# AUDIO_CODEC.net
KiCad netlist of a schematic drawn in Altium Designer
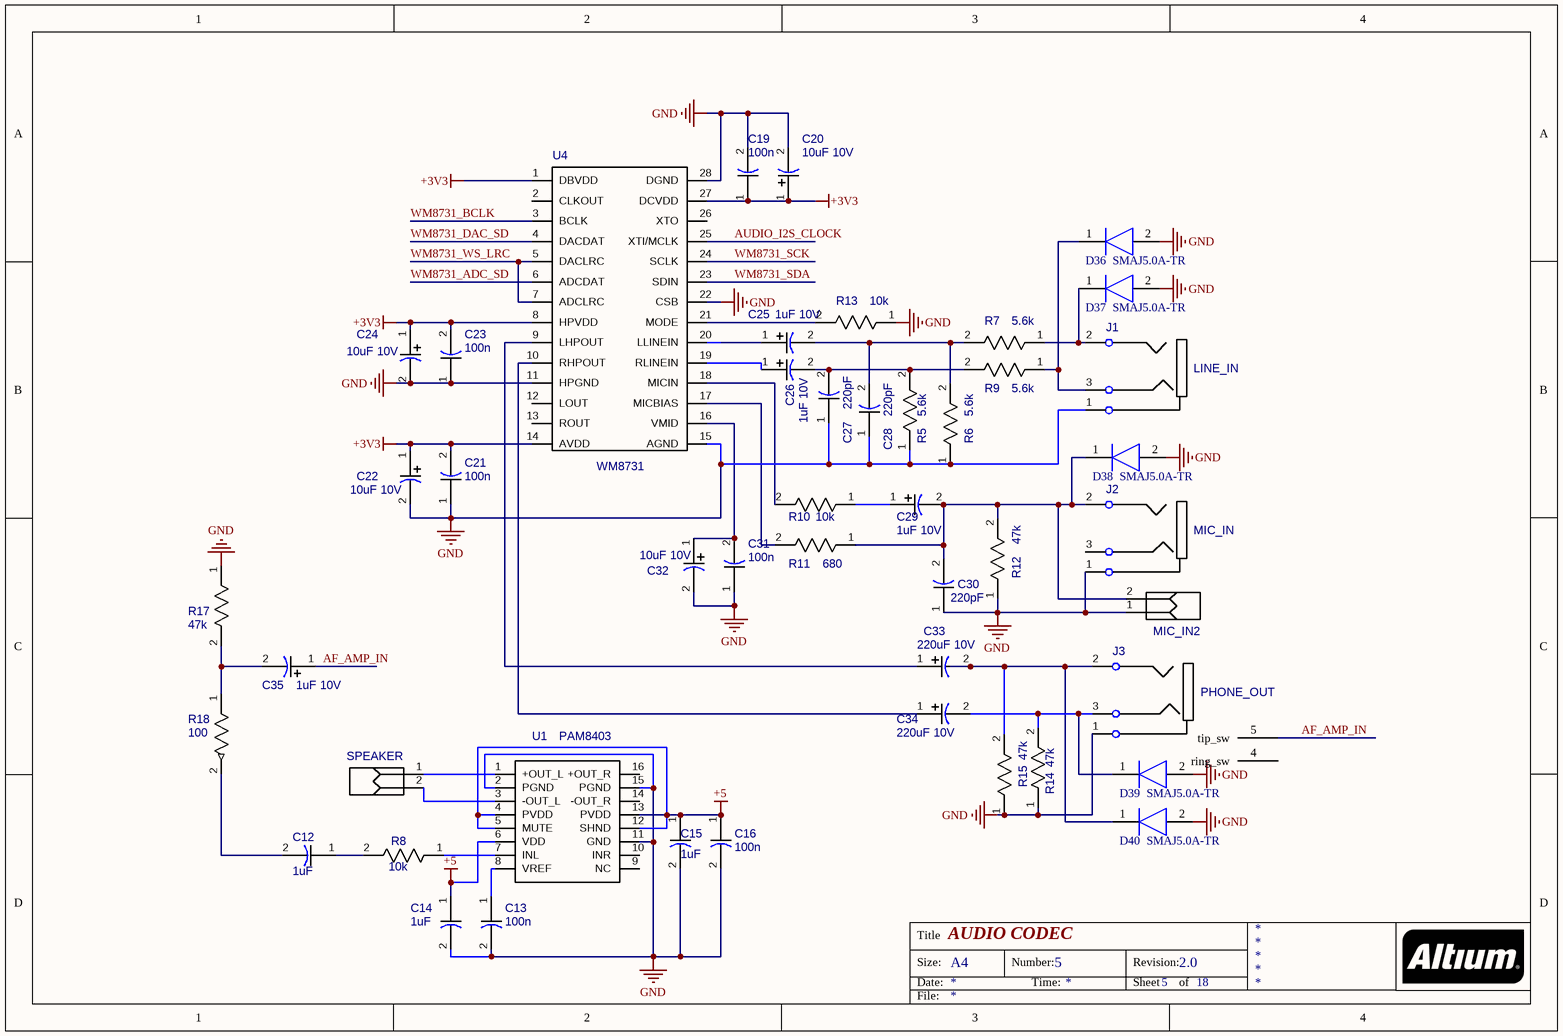
[diagram p0: AUDIO CODEC.SchDoc]

(export (version "E")
  (design (tool "Eeschema 10.0.6"))
  (components
    (comp (ref "C12")
      (value "1uF")
      (footprint "CAP_0805")
      (description "CAP_0805")
      (libsource (lib "*") (part "CAP_0805"))
    )
    (comp (ref "C13")
      (value "100n")
      (footprint "CAP_0805")
      (description "CAP_0805")
      (libsource (lib "*") (part "CAP_0805"))
    )
    (comp (ref "C14")
      (value "1uF")
      (footprint "CAP_0805")
      (description "CAP_0805")
      (libsource (lib "*") (part "CAP_0805"))
    )
    (comp (ref "C15")
      (value "1uF")
      (footprint "CAP_0805")
      (description "CAP_0805")
      (libsource (lib "*") (part "CAP_0805"))
    )
    (comp (ref "C16")
      (value "100n")
      (footprint "CAP_0805")
      (description "CAP_0805")
      (libsource (lib "*") (part "CAP_0805"))
    )
    (comp (ref "C19")
      (value "100n")
      (footprint "CAP_0805")
      (description "CAP_0805")
      (libsource (lib "*") (part "CAP_0805"))
    )
    (comp (ref "C20")
      (value "10uF 10V")
      (footprint "CAPAE_4.3x4.3h5.4")
      (description "CAPAE_4.3x4.3h5.4")
      (libsource (lib "*") (part "CAPAE_4.3x4.3h5.4"))
    )
    (comp (ref "C21")
      (value "100n")
      (footprint "CAP_0805")
      (description "CAP_0805")
      (libsource (lib "*") (part "CAP_0805"))
    )
    (comp (ref "C22")
      (value "10uF 10V")
      (footprint "CAPAE_4.3x4.3h5.4")
      (description "CAPAE_4.3x4.3h5.4")
      (libsource (lib "*") (part "CAPAE_4.3x4.3h5.4"))
    )
    (comp (ref "C23")
      (value "100n")
      (footprint "CAP_0805")
      (description "CAP_0805")
      (libsource (lib "*") (part "CAP_0805"))
    )
    (comp (ref "C24")
      (value "10uF 10V")
      (footprint "CAPAE_4.3x4.3h5.4")
      (description "CAPAE_4.3x4.3h5.4")
      (libsource (lib "*") (part "CAPAE_4.3x4.3h5.4"))
    )
    (comp (ref "C25")
      (value "1uF 10V")
      (footprint "CAPAE_4.3x4.3h5.4")
      (description "CAPAE_4.3x4.3h5.4")
      (libsource (lib "*") (part "CAPAE_4.3x4.3h5.4"))
    )
    (comp (ref "C26")
      (value "1uF 10V")
      (footprint "CAPAE_4.3x4.3h5.4")
      (description "CAPAE_4.3x4.3h5.4")
      (libsource (lib "*") (part "CAPAE_4.3x4.3h5.4"))
    )
    (comp (ref "C27")
      (value "220pF")
      (footprint "CAP_0805")
      (description "CAP_0805")
      (libsource (lib "*") (part "CAP_0805"))
    )
    (comp (ref "C28")
      (value "220pF")
      (footprint "CAP_0805")
      (description "CAP_0805")
      (libsource (lib "*") (part "CAP_0805"))
    )
    (comp (ref "C29")
      (value "1uF 10V")
      (footprint "CAPAE_4.3x4.3h5.4")
      (description "CAPAE_4.3x4.3h5.4")
      (libsource (lib "*") (part "CAPAE_4.3x4.3h5.4"))
    )
    (comp (ref "C30")
      (value "220pF")
      (footprint "CAP_0805")
      (description "CAP_0805")
      (libsource (lib "*") (part "CAP_0805"))
    )
    (comp (ref "C31")
      (value "100n")
      (footprint "CAP_0805")
      (description "CAP_0805")
      (libsource (lib "*") (part "CAP_0805"))
    )
    (comp (ref "C32")
      (value "10uF 10V")
      (footprint "CAPAE_4.3x4.3h5.4")
      (description "CAPAE_4.3x4.3h5.4")
      (libsource (lib "*") (part "CAPAE_4.3x4.3h5.4"))
    )
    (comp (ref "C33")
      (value "220uF 10V")
      (footprint "CAPAE_4.3x4.3h5.4")
      (description "CAPAE_4.3x4.3h5.4")
      (libsource (lib "*") (part "CAPAE_4.3x4.3h5.4"))
    )
    (comp (ref "C34")
      (value "220uF 10V")
      (footprint "CAPAE_4.3x4.3h5.4")
      (description "CAPAE_4.3x4.3h5.4")
      (libsource (lib "*") (part "CAPAE_4.3x4.3h5.4"))
    )
    (comp (ref "C35")
      (value "1uF 10V")
      (footprint "CAPAE_4.3x4.3h5.4")
      (description "CAPAE_4.3x4.3h5.4")
      (libsource (lib "*") (part "CAPAE_4.3x4.3h5.4"))
    )
    (comp (ref "D36")
      (value "SMAJ5.0A-TR")
      (footprint "SamacSys:SMBJ36CATR")
      (description "Diode")
      (fields
        (field (name "MANUFACTURER_PART_NUMBER") "SMLVT3V3")
        (field (name "MOUSER PART NUMBER") "511-SMLVT3V3")
      )
      (libsource (lib "*") (part "SMLVT3V3"))
    )
    (comp (ref "D37")
      (value "SMAJ5.0A-TR")
      (footprint "SamacSys:SMBJ36CATR")
      (description "Diode")
      (fields
        (field (name "MANUFACTURER_PART_NUMBER") "SMLVT3V3")
        (field (name "MOUSER PART NUMBER") "511-SMLVT3V3")
      )
      (libsource (lib "*") (part "SMLVT3V3"))
    )
    (comp (ref "D38")
      (value "SMAJ5.0A-TR")
      (footprint "SamacSys:SMBJ36CATR")
      (description "Diode")
      (fields
        (field (name "MANUFACTURER_PART_NUMBER") "SMLVT3V3")
        (field (name "MOUSER PART NUMBER") "511-SMLVT3V3")
      )
      (libsource (lib "*") (part "SMLVT3V3"))
    )
    (comp (ref "D39")
      (value "SMAJ5.0A-TR")
      (footprint "SamacSys:SMBJ36CATR")
      (description "Diode")
      (fields
        (field (name "MANUFACTURER_PART_NUMBER") "SMLVT3V3")
        (field (name "MOUSER PART NUMBER") "511-SMLVT3V3")
      )
      (libsource (lib "*") (part "SMLVT3V3"))
    )
    (comp (ref "D40")
      (value "SMAJ5.0A-TR")
      (footprint "SamacSys:SMBJ36CATR")
      (description "Diode")
      (fields
        (field (name "MANUFACTURER_PART_NUMBER") "SMLVT3V3")
        (field (name "MOUSER PART NUMBER") "511-SMLVT3V3")
      )
      (libsource (lib "*") (part "SMLVT3V3"))
    )
    (comp (ref "J1")
      (value "LINE_IN")
      (footprint "SJ1-3525NG")
      (description "SJ1-3525NG")
      (libsource (lib "*") (part "SJ1-3523N"))
    )
    (comp (ref "J2")
      (value "MIC_IN")
      (footprint "SJ1-3525NG")
      (description "SJ1-3525NG")
      (libsource (lib "*") (part "SJ1-3523N"))
    )
    (comp (ref "J3")
      (value "PHONE_OUT")
      (footprint "SJ1-3525NG")
      (description "SJ1-3525NG")
      (libsource (lib "") (part "SJ1-3523N_1"))
    )
    (comp (ref "MIС_IN2")
      (value "MIС_IN2")
      (footprint "51022-0200")
      (description "2 Pin")
      (libsource (lib "*") (part "51022-0200"))
    )
    (comp (ref "R5")
      (value "5.6k")
      (footprint "RES_0805")
      (description "RES_0805")
      (libsource (lib "*") (part "RES_0805"))
    )
    (comp (ref "R6")
      (value "5.6k")
      (footprint "RES_0805")
      (description "RES_0805")
      (libsource (lib "*") (part "RES_0805"))
    )
    (comp (ref "R7")
      (value "5.6k")
      (footprint "RES_0805")
      (description "RES_0805")
      (libsource (lib "*") (part "RES_0805"))
    )
    (comp (ref "R8")
      (value "10k")
      (footprint "RES_0805")
      (description "RES_0805")
      (libsource (lib "*") (part "RES_0805"))
    )
    (comp (ref "R9")
      (value "5.6k")
      (footprint "RES_0805")
      (description "RES_0805")
      (libsource (lib "*") (part "RES_0805"))
    )
    (comp (ref "R10")
      (value "10k")
      (footprint "RES_0805")
      (description "RES_0805")
      (libsource (lib "*") (part "RES_0805"))
    )
    (comp (ref "R11")
      (value "680")
      (footprint "RES_0805")
      (description "RES_0805")
      (libsource (lib "*") (part "RES_0805"))
    )
    (comp (ref "R12")
      (value "47k")
      (footprint "RES_0805")
      (description "RES_0805")
      (libsource (lib "*") (part "RES_0805"))
    )
    (comp (ref "R13")
      (value "10k")
      (footprint "RES_0805")
      (description "RES_0805")
      (libsource (lib "*") (part "RES_0805"))
    )
    (comp (ref "R14")
      (value "47k")
      (footprint "RES_0805")
      (description "RES_0805")
      (libsource (lib "*") (part "RES_0805"))
    )
    (comp (ref "R15")
      (value "47k")
      (footprint "RES_0805")
      (description "RES_0805")
      (libsource (lib "*") (part "RES_0805"))
    )
    (comp (ref "R17")
      (value "47k")
      (footprint "RES_0805")
      (description "RES_0805")
      (libsource (lib "*") (part "RES_0805"))
    )
    (comp (ref "R18")
      (value "100")
      (footprint "RES_0805")
      (description "RES_0805")
      (libsource (lib "*") (part "RES_0805"))
    )
    (comp (ref "SPEAKER")
      (value "~")
      (footprint "51022-0200")
      (description "51022-0200")
      (libsource (lib "*") (part "51022-0200"))
    )
    (comp (ref "U1") (value "PAM8403") (footprint "PAM8403") (libsource (lib "*") (part "PAM8403")))
    (comp (ref "U4") (value "WM8731") (footprint "WM8731") (libsource (lib "*") (part "WM8731")))
  )
  (nets
    (net (code "1") (name "+3V3") (class "Default")
      (node (ref "C19") (pin "1") (pinfunction "1_1") (pintype "passive"))
      (node (ref "C20") (pin "1") (pinfunction "PLUS_1") (pintype "passive"))
      (node (ref "C21") (pin "2") (pinfunction "2_2") (pintype "passive"))
      (node (ref "C22") (pin "1") (pinfunction "PLUS_1") (pintype "passive"))
      (node (ref "C23") (pin "2") (pinfunction "2_2") (pintype "passive"))
      (node (ref "C24") (pin "1") (pinfunction "PLUS_1") (pintype "passive"))
      (node (ref "U4") (pin "1") (pinfunction "DBVDD_1") (pintype "passive"))
      (node (ref "U4") (pin "14") (pinfunction "AVDD_14") (pintype "passive"))
      (node (ref "U4") (pin "27") (pinfunction "DCVDD_27") (pintype "passive"))
      (node (ref "U4") (pin "8") (pinfunction "HPVDD_8") (pintype "passive"))
    )
    (net (code "2") (name "+5") (class "Default")
      (node (ref "C14") (pin "1") (pinfunction "1_1") (pintype "passive"))
      (node (ref "C15") (pin "1") (pinfunction "1_1") (pintype "passive"))
      (node (ref "C16") (pin "1") (pinfunction "1_1") (pintype "passive"))
      (node (ref "U1") (pin "12") (pinfunction "SHND_12") (pintype "passive"))
      (node (ref "U1") (pin "13") (pinfunction "PVDD_13") (pintype "passive"))
      (node (ref "U1") (pin "4") (pinfunction "PVDD_4") (pintype "passive"))
      (node (ref "U1") (pin "5") (pinfunction "MUTE_5") (pintype "passive"))
      (node (ref "U1") (pin "6") (pinfunction "VDD_6") (pintype "passive"))
    )
    (net (code "3") (name "/AF_AMP_IN") (class "Default")
      (node (ref "C35") (pin "1") (pinfunction "PLUS_1") (pintype "passive"))
      (node (ref "J3") (pin "5") (pinfunction "tip_sw_5") (pintype "passive"))
    )
    (net (code "4") (name "/AUDIO_I2S_CLOCK") (class "Default")
      (node (ref "U4") (pin "25") (pinfunction "XTI/MCLK_25") (pintype "passive"))
    )
    (net (code "5") (name "/WM8731_ADC_SD") (class "Default")
      (node (ref "U4") (pin "6") (pinfunction "ADCDAT_6") (pintype "passive"))
    )
    (net (code "6") (name "/WM8731_BCLK") (class "Default")
      (node (ref "U4") (pin "3") (pinfunction "BCLK_3") (pintype "passive"))
    )
    (net (code "7") (name "/WM8731_DAC_SD") (class "Default")
      (node (ref "U4") (pin "4") (pinfunction "DACDAT_4") (pintype "passive"))
    )
    (net (code "8") (name "/WM8731_SCK") (class "Default")
      (node (ref "U4") (pin "24") (pinfunction "SCLK_24") (pintype "passive"))
    )
    (net (code "9") (name "/WM8731_SDA") (class "Default")
      (node (ref "U4") (pin "23") (pinfunction "SDIN_23") (pintype "passive"))
    )
    (net (code "10") (name "/WM8731_WS_LRC") (class "Default")
      (node (ref "U4") (pin "5") (pinfunction "DACLRC_5") (pintype "passive"))
      (node (ref "U4") (pin "7") (pinfunction "ADCLRC_7") (pintype "passive"))
    )
    (net (code "11") (name "GND") (class "Default")
      (node (ref "C13") (pin "2") (pinfunction "2_2") (pintype "passive"))
      (node (ref "C14") (pin "2") (pinfunction "2_2") (pintype "passive"))
      (node (ref "C15") (pin "2") (pinfunction "2_2") (pintype "passive"))
      (node (ref "C16") (pin "2") (pinfunction "2_2") (pintype "passive"))
      (node (ref "C19") (pin "2") (pinfunction "2_2") (pintype "passive"))
      (node (ref "C20") (pin "2") (pinfunction "MINUS_2") (pintype "passive"))
      (node (ref "C21") (pin "1") (pinfunction "1_1") (pintype "passive"))
      (node (ref "C22") (pin "2") (pinfunction "MINUS_2") (pintype "passive"))
      (node (ref "C23") (pin "1") (pinfunction "1_1") (pintype "passive"))
      (node (ref "C24") (pin "2") (pinfunction "MINUS_2") (pintype "passive"))
      (node (ref "C27") (pin "1") (pinfunction "1_1") (pintype "passive"))
      (node (ref "C28") (pin "1") (pinfunction "1_1") (pintype "passive"))
      (node (ref "C30") (pin "1") (pinfunction "1_1") (pintype "passive"))
      (node (ref "C31") (pin "1") (pinfunction "1_1") (pintype "passive"))
      (node (ref "C32") (pin "2") (pinfunction "MINUS_2") (pintype "passive"))
      (node (ref "D36") (pin "2") (pinfunction "A_2") (pintype "passive"))
      (node (ref "D37") (pin "2") (pinfunction "A_2") (pintype "passive"))
      (node (ref "D38") (pin "2") (pinfunction "A_2") (pintype "passive"))
      (node (ref "D39") (pin "2") (pinfunction "A_2") (pintype "passive"))
      (node (ref "D40") (pin "2") (pinfunction "A_2") (pintype "passive"))
      (node (ref "J1") (pin "1") (pinfunction "sleeve_1") (pintype "passive"))
      (node (ref "J2") (pin "1") (pinfunction "sleeve_1") (pintype "passive"))
      (node (ref "J3") (pin "1") (pinfunction "sleeve_1") (pintype "passive"))
      (node (ref "MIС_IN2") (pin "1") (pinfunction "1_1") (pintype "passive"))
      (node (ref "R12") (pin "1") (pinfunction "1_1") (pintype "passive"))
      (node (ref "R13") (pin "1") (pinfunction "1_1") (pintype "passive"))
      (node (ref "R14") (pin "1") (pinfunction "1_1") (pintype "passive"))
      (node (ref "R15") (pin "1") (pinfunction "1_1") (pintype "passive"))
      (node (ref "R17") (pin "1") (pinfunction "1_1") (pintype "passive"))
      (node (ref "R5") (pin "1") (pinfunction "1_1") (pintype "passive"))
      (node (ref "R6") (pin "1") (pinfunction "1_1") (pintype "passive"))
      (node (ref "U1") (pin "11") (pinfunction "GND_11") (pintype "passive"))
      (node (ref "U1") (pin "15") (pinfunction "PGND_15") (pintype "passive"))
      (node (ref "U1") (pin "2") (pinfunction "PGND_2") (pintype "passive"))
      (node (ref "U4") (pin "11") (pinfunction "HPGND_11") (pintype "passive"))
      (node (ref "U4") (pin "15") (pinfunction "AGND_15") (pintype "passive"))
      (node (ref "U4") (pin "22") (pinfunction "CSB_22") (pintype "passive"))
      (node (ref "U4") (pin "28") (pinfunction "DGND_28") (pintype "passive"))
    )
    (net (code "12") (name "Net-(C12-Pad1)") (class "Default")
      (node (ref "C12") (pin "1") (pinfunction "1_1") (pintype "passive"))
      (node (ref "R8") (pin "2") (pinfunction "2_2") (pintype "passive"))
    )
    (net (code "13") (name "Net-(C12-Pad2)") (class "Default")
      (node (ref "C12") (pin "2") (pinfunction "2_2") (pintype "passive"))
      (node (ref "R18") (pin "2") (pinfunction "2_2") (pintype "passive"))
    )
    (net (code "14") (name "Net-(C25-MINUS)") (class "Default")
      (node (ref "C25") (pin "2") (pinfunction "MINUS_2") (pintype "passive"))
      (node (ref "C28") (pin "2") (pinfunction "2_2") (pintype "passive"))
      (node (ref "R6") (pin "2") (pinfunction "2_2") (pintype "passive"))
      (node (ref "R7") (pin "2") (pinfunction "2_2") (pintype "passive"))
    )
    (net (code "15") (name "Net-(C25-PLUS)") (class "Default")
      (node (ref "C25") (pin "1") (pinfunction "PLUS_1") (pintype "passive"))
      (node (ref "U4") (pin "20") (pinfunction "LLINEIN_20") (pintype "passive"))
    )
    (net (code "16") (name "Net-(C26-MINUS)") (class "Default")
      (node (ref "C26") (pin "2") (pinfunction "MINUS_2") (pintype "passive"))
      (node (ref "C27") (pin "2") (pinfunction "2_2") (pintype "passive"))
      (node (ref "R5") (pin "2") (pinfunction "2_2") (pintype "passive"))
      (node (ref "R9") (pin "2") (pinfunction "2_2") (pintype "passive"))
    )
    (net (code "17") (name "Net-(C26-PLUS)") (class "Default")
      (node (ref "C26") (pin "1") (pinfunction "PLUS_1") (pintype "passive"))
      (node (ref "U4") (pin "19") (pinfunction "RLINEIN_19") (pintype "passive"))
    )
    (net (code "18") (name "Net-(C29-MINUS)") (class "Default")
      (node (ref "C29") (pin "2") (pinfunction "MINUS_2") (pintype "passive"))
      (node (ref "C30") (pin "2") (pinfunction "2_2") (pintype "passive"))
      (node (ref "D38") (pin "1") (pinfunction "K_1") (pintype "passive"))
      (node (ref "J2") (pin "2") (pinfunction "tip_2") (pintype "passive"))
      (node (ref "MIС_IN2") (pin "2") (pinfunction "2_2") (pintype "passive"))
      (node (ref "R11") (pin "1") (pinfunction "1_1") (pintype "passive"))
      (node (ref "R12") (pin "2") (pinfunction "2_2") (pintype "passive"))
    )
    (net (code "19") (name "Net-(C29-PLUS)") (class "Default")
      (node (ref "C29") (pin "1") (pinfunction "PLUS_1") (pintype "passive"))
      (node (ref "R10") (pin "1") (pinfunction "1_1") (pintype "passive"))
    )
    (net (code "20") (name "Net-(C32-PLUS)") (class "Default")
      (node (ref "C31") (pin "2") (pinfunction "2_2") (pintype "passive"))
      (node (ref "C32") (pin "1") (pinfunction "PLUS_1") (pintype "passive"))
      (node (ref "U4") (pin "16") (pinfunction "VMID_16") (pintype "passive"))
    )
    (net (code "21") (name "Net-(C33-MINUS)") (class "Default")
      (node (ref "C33") (pin "2") (pinfunction "MINUS_2") (pintype "passive"))
      (node (ref "D40") (pin "1") (pinfunction "K_1") (pintype "passive"))
      (node (ref "J3") (pin "2") (pinfunction "tip_2") (pintype "passive"))
      (node (ref "R15") (pin "2") (pinfunction "2_2") (pintype "passive"))
    )
    (net (code "22") (name "Net-(C33-PLUS)") (class "Default")
      (node (ref "C33") (pin "1") (pinfunction "PLUS_1") (pintype "passive"))
      (node (ref "U4") (pin "9") (pinfunction "LHPOUT_9") (pintype "passive"))
    )
    (net (code "23") (name "Net-(C34-MINUS)") (class "Default")
      (node (ref "C34") (pin "2") (pinfunction "MINUS_2") (pintype "passive"))
      (node (ref "D39") (pin "1") (pinfunction "K_1") (pintype "passive"))
      (node (ref "J3") (pin "3") (pinfunction "ring_3") (pintype "passive"))
      (node (ref "R14") (pin "2") (pinfunction "2_2") (pintype "passive"))
    )
    (net (code "24") (name "Net-(C34-PLUS)") (class "Default")
      (node (ref "C34") (pin "1") (pinfunction "PLUS_1") (pintype "passive"))
      (node (ref "U4") (pin "10") (pinfunction "RHPOUT_10") (pintype "passive"))
    )
    (net (code "25") (name "Net-(C35-MINUS)") (class "Default")
      (node (ref "C35") (pin "2") (pinfunction "MINUS_2") (pintype "passive"))
      (node (ref "R17") (pin "2") (pinfunction "2_2") (pintype "passive"))
      (node (ref "R18") (pin "1") (pinfunction "1_1") (pintype "passive"))
    )
    (net (code "26") (name "Net-(D36-K)") (class "Default")
      (node (ref "D36") (pin "1") (pinfunction "K_1") (pintype "passive"))
      (node (ref "J1") (pin "3") (pinfunction "ring_3") (pintype "passive"))
      (node (ref "R9") (pin "1") (pinfunction "1_1") (pintype "passive"))
    )
    (net (code "27") (name "Net-(D37-K)") (class "Default")
      (node (ref "D37") (pin "1") (pinfunction "K_1") (pintype "passive"))
      (node (ref "J1") (pin "2") (pinfunction "tip_2") (pintype "passive"))
      (node (ref "R7") (pin "1") (pinfunction "1_1") (pintype "passive"))
    )
    (net (code "28") (name "Net-(U1-+OUT_L)") (class "Default")
      (node (ref "SPEAKER") (pin "1") (pinfunction "1_1") (pintype "passive"))
      (node (ref "U1") (pin "1") (pinfunction "+OUT_L_1") (pintype "passive"))
    )
    (net (code "29") (name "Net-(U1--OUT_L)") (class "Default")
      (node (ref "SPEAKER") (pin "2") (pinfunction "2_2") (pintype "passive"))
      (node (ref "U1") (pin "3") (pinfunction "-OUT_L_3") (pintype "passive"))
    )
    (net (code "30") (name "Net-(U1-INL)") (class "Default")
      (node (ref "R8") (pin "1") (pinfunction "1_1") (pintype "passive"))
      (node (ref "U1") (pin "7") (pinfunction "INL_7") (pintype "passive"))
    )
    (net (code "31") (name "Net-(U1-VREF)") (class "Default")
      (node (ref "C13") (pin "1") (pinfunction "1_1") (pintype "passive"))
      (node (ref "U1") (pin "8") (pinfunction "VREF_8") (pintype "passive"))
    )
    (net (code "32") (name "Net-(U4-MICBIAS)") (class "Default")
      (node (ref "R11") (pin "2") (pinfunction "2_2") (pintype "passive"))
      (node (ref "U4") (pin "17") (pinfunction "MICBIAS_17") (pintype "passive"))
    )
    (net (code "33") (name "Net-(U4-MICIN)") (class "Default")
      (node (ref "R10") (pin "2") (pinfunction "2_2") (pintype "passive"))
      (node (ref "U4") (pin "18") (pinfunction "MICIN_18") (pintype "passive"))
    )
    (net (code "34") (name "Net-(U4-MODE)") (class "Default")
      (node (ref "R13") (pin "2") (pinfunction "2_2") (pintype "passive"))
      (node (ref "U4") (pin "21") (pinfunction "MODE_21") (pintype "passive"))
    )
    (net (code "35") (name "unconnected-(J2-ring-Pad3)") (class "Default")
      (node (ref "J2") (pin "3") (pinfunction "ring_3") (pintype "passive"))
    )
    (net (code "36") (name "unconnected-(J3-ring_sw-Pad4)") (class "Default")
      (node (ref "J3") (pin "4") (pinfunction "ring_sw_4") (pintype "passive"))
    )
    (net (code "37") (name "unconnected-(U1-+OUT_R-Pad16)") (class "Default")
      (node (ref "U1") (pin "16") (pinfunction "+OUT_R_16") (pintype "passive"))
    )
    (net (code "38") (name "unconnected-(U1--OUT_R-Pad14)") (class "Default")
      (node (ref "U1") (pin "14") (pinfunction "-OUT_R_14") (pintype "passive"))
    )
    (net (code "39") (name "unconnected-(U1-INR-Pad10)") (class "Default")
      (node (ref "U1") (pin "10") (pinfunction "INR_10") (pintype "passive"))
    )
    (net (code "40") (name "unconnected-(U1-NC-Pad9)") (class "Default")
      (node (ref "U1") (pin "9") (pinfunction "NC_9") (pintype "passive"))
    )
    (net (code "41") (name "unconnected-(U4-CLKOUT-Pad2)") (class "Default")
      (node (ref "U4") (pin "2") (pinfunction "CLKOUT_2") (pintype "passive"))
    )
    (net (code "42") (name "unconnected-(U4-LOUT-Pad12)") (class "Default")
      (node (ref "U4") (pin "12") (pinfunction "LOUT_12") (pintype "passive"))
    )
    (net (code "43") (name "unconnected-(U4-ROUT-Pad13)") (class "Default")
      (node (ref "U4") (pin "13") (pinfunction "ROUT_13") (pintype "passive"))
    )
    (net (code "44") (name "unconnected-(U4-XTO-Pad26)") (class "Default")
      (node (ref "U4") (pin "26") (pinfunction "XTO_26") (pintype "passive"))
    )
  )
)
